# NST_output.net
KiCad netlist of a schematic drawn in EAGLE
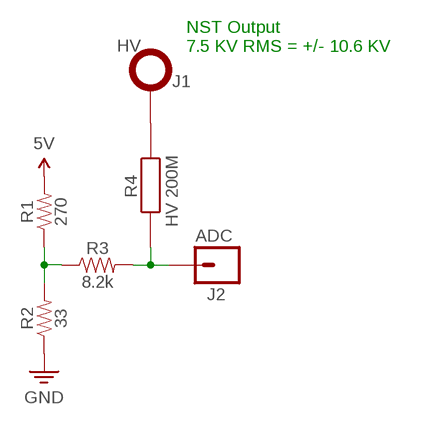
[diagram p0: schematic, sheet 1]

(export (version "E")
  (design (tool "Eeschema 10.0.6"))
  (components
    (comp (ref "J1")
      (value "HV")
      (footprint "eagle-import:LUG_SQUARE_M6")
      (libsource (lib "eagle-import") (part "TERMINAL_M6"))
    )
    (comp (ref "J2")
      (value "ADC")
      (footprint "eagle-import:1X01_2MM")
      (libsource (lib "eagle-import") (part "CONN_01PTH_2MM"))
    )
    (comp (ref "R1")
      (value "270")
      (footprint "eagle-import:AXIAL-0.3")
      (libsource (lib "eagle-import") (part "15KOHM-HORIZ-1/4W-5%"))
    )
    (comp (ref "R2")
      (value "33")
      (footprint "eagle-import:AXIAL-0.3")
      (libsource (lib "eagle-import") (part "15KOHM-HORIZ-1/4W-5%"))
    )
    (comp (ref "R3")
      (value "8.2k")
      (footprint "eagle-import:AXIAL-0.3")
      (libsource (lib "eagle-import") (part "15KOHM-HORIZ-1/4W-5%"))
    )
    (comp (ref "R4")
      (value "HV 200M")
      (footprint "eagle-import:SM108031007FE")
      (fields
        (field (name "MANUFACTURER_PART_NUMBER") "SM108031005FE")
        (field (name "RS_PART_NUMBER") "8927338")
      )
      (libsource (lib "eagle-import") (part "SM108031005FE"))
    )
  )
  (nets
    (net (code "1") (name "5V") (class "Default")
      (node (ref "R1") (pin "P$2") (pinfunction "2_P$2") (pintype "passive"))
    )
    (net (code "2") (name "GND") (class "Default")
      (node (ref "R2") (pin "P$1") (pinfunction "1_P$1") (pintype "passive"))
    )
    (net (code "3") (name "Net-(J1-PadP$1)") (class "Default")
      (node (ref "J1") (pin "P$1") (pinfunction "P$1_P$1") (pintype "passive"))
      (node (ref "R4") (pin "2") (pinfunction "2_2") (pintype "bidirectional"))
    )
    (net (code "4") (name "Net-(R1-1)") (class "Default")
      (node (ref "R1") (pin "P$1") (pinfunction "1_P$1") (pintype "passive"))
      (node (ref "R2") (pin "P$2") (pinfunction "2_P$2") (pintype "passive"))
      (node (ref "R3") (pin "P$1") (pinfunction "1_P$1") (pintype "passive"))
    )
    (net (code "5") (name "Net-(R3-2)") (class "Default")
      (node (ref "J2") (pin "1") (pinfunction "1_1") (pintype "passive"))
      (node (ref "R3") (pin "P$2") (pinfunction "2_P$2") (pintype "passive"))
      (node (ref "R4") (pin "1") (pinfunction "1_1") (pintype "bidirectional"))
    )
  )
)
